# 1WB_DS2406_EPROM.net
KiCad netlist of a schematic drawn in Altium Designer
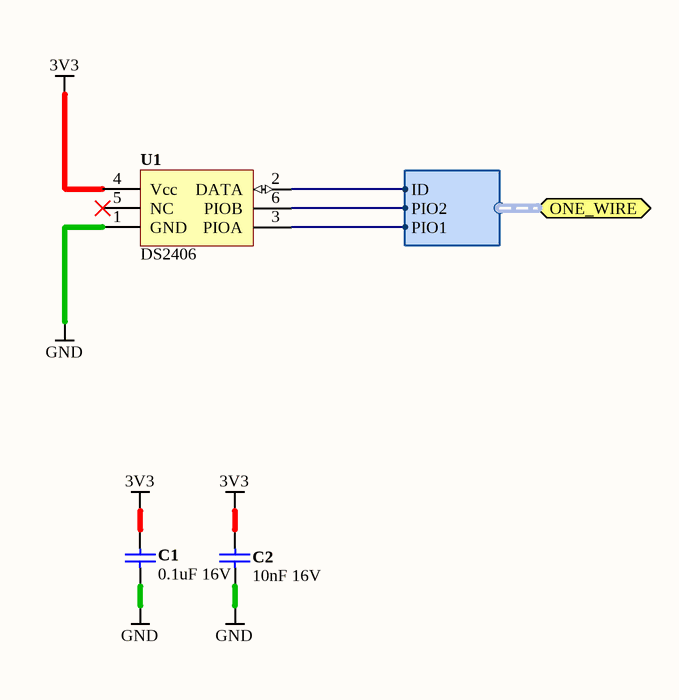
[diagram p0: 1WB_DS2406_EPROM.SchDoc]

(export (version "E")
  (design (tool "Eeschema 10.0.6"))
  (components
    (comp (ref "C1")
      (value "0.1uF 16V")
      (footprint "CAPC1005-STAR")
      (description "Capacitor, Ceramic, 0.1uF 10% 16V 0402 (1005) X7R")
      (fields (field (name "TOLERANCE") "10 %"))
      (libsource (lib "AltiumDesignLibrary") (part "CAP-NP"))
    )
    (comp (ref "C2")
      (value "10nF 16V")
      (footprint "CAPC1005-STAR")
      (description "Capacitor, Ceramic, 10nF 10% 16V 0402 (1005) X7R")
      (fields (field (name "TOLERANCE") "10 %"))
      (libsource (lib "AltiumDesignLibrary") (part "CAP-NP"))
    )
    (comp (ref "U1")
      (value "DS2406")
      (footprint "TSOC6")
      (description "Dual Addressable Switch Plus 1KB Memory")
      (libsource (lib "AltiumDesignLibrary") (part "DS2406"))
    )
  )
  (nets
    (net (code "2") (name "/ID") (class "Default")
      (node (ref "U1") (pin "2") (pinfunction "DATA_2") (pintype "bidirectional"))
    )
    (net (code "3") (name "/PIO1") (class "Default")
      (node (ref "U1") (pin "3") (pinfunction "PIOA_3") (pintype "open_collector"))
    )
    (net (code "4") (name "/PIO2") (class "Default")
      (node (ref "U1") (pin "6") (pinfunction "PIOB_6") (pintype "passive"))
    )
    (net (code "6") (name "3V3") (class "Default")
      (node (ref "C1") (pin "2") (pinfunction "2_2") (pintype "passive"))
      (node (ref "C2") (pin "1") (pinfunction "1_1") (pintype "passive"))
      (node (ref "U1") (pin "4") (pinfunction "Vcc_4") (pintype "passive"))
    )
    (net (code "7") (name "GND") (class "Default")
      (node (ref "C1") (pin "1") (pinfunction "1_1") (pintype "passive"))
      (node (ref "C2") (pin "2") (pinfunction "2_2") (pintype "passive"))
      (node (ref "U1") (pin "1") (pinfunction "GND_1") (pintype "power_in"))
    )
    (net (code "8") (name "unconnected-(U1-NC-Pad5)") (class "Default")
      (node (ref "U1") (pin "5") (pinfunction "NC_5") (pintype "passive+no_connect"))
    )
  )
)
